# 01_giris.net
KiCad netlist of a schematic drawn in Altium Designer
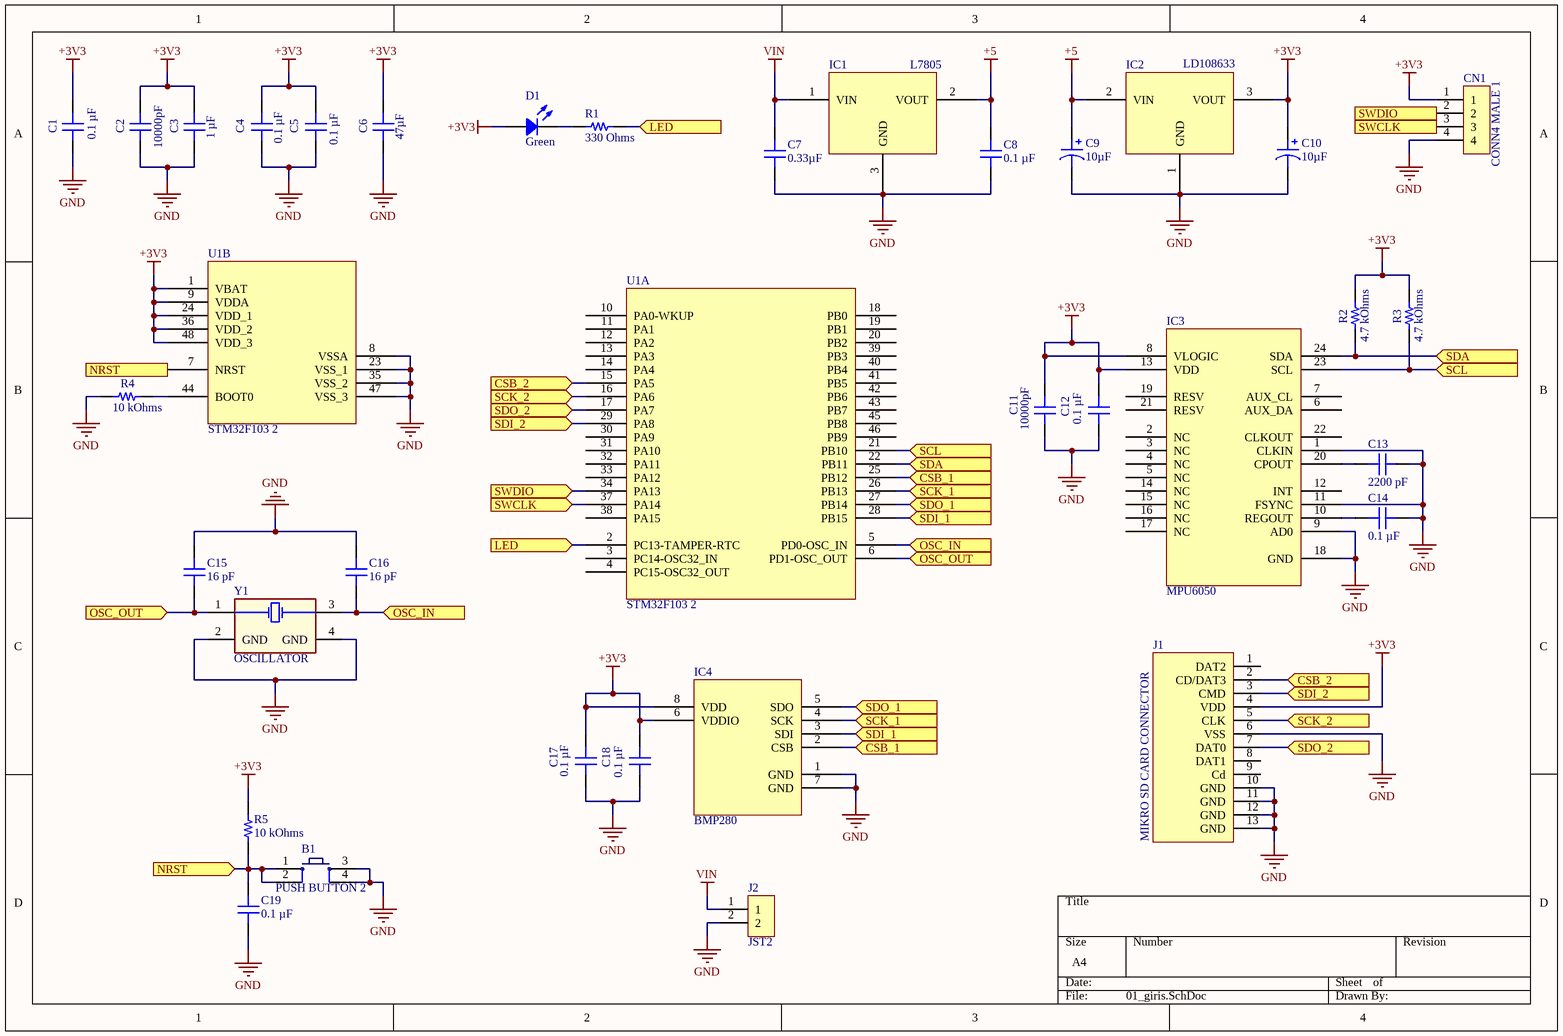
[diagram p0: 01_giris.SchDoc]

(export (version "E")
  (design (tool "Eeschema 10.0.6"))
  (components
    (comp (ref "B1")
      (value "PUSH BUTTON 2")
      (footprint "PUSH BUTTON 2")
      (libsource (lib "AltiumilePcbCizimi_Library") (part "PUSH BUTTON 2"))
    )
    (comp (ref "C1")
      (value "0.1 µF")
      (footprint "CAP 1206_3216 - 0.8MM")
      (description "CAP CER 0.1UF 50V X7R 1206")
      (fields
        (field (name "PART NUMBER") "1206B104M500CT")
        (field (name "MANUFACTURER") "Walsin Technology Corporation")
      )
      (libsource (lib "Celestial Altium Library - altium_library") (part "Capacitor"))
    )
    (comp (ref "C2")
      (value "10000pF")
      (footprint "CAP 1206_3216 - 1.0MM")
      (description "CAP CER 10000PF 50V X7R 1206")
      (fields (field (name "PART NUMBER") "12065C103K4T2A") (field (name "MANUFACTURER") "AVX Corporation"))
      (libsource (lib "Celestial Altium Library - altium_library") (part "Capacitor"))
    )
    (comp (ref "C3")
      (value "1 µF")
      (footprint "CAP 1206_3216 - 0.8MM")
      (description "CAP CER 1206 1UF 25V X7R")
      (fields (field (name "PART NUMBER") "C1206X105K3RAC3316") (field (name "MANUFACTURER") "KEMET"))
      (libsource (lib "Celestial Altium Library - altium_library") (part "Capacitor"))
    )
    (comp (ref "C4")
      (value "0.1 µF")
      (footprint "CAP 1206_3216 - 0.8MM")
      (description "CAP CER 0.1UF 50V X7R 1206")
      (fields
        (field (name "PART NUMBER") "1206B104M500CT")
        (field (name "MANUFACTURER") "Walsin Technology Corporation")
      )
      (libsource (lib "Celestial Altium Library - altium_library") (part "Capacitor"))
    )
    (comp (ref "C5")
      (value "0.1 µF")
      (footprint "CAP 1206_3216 - 0.8MM")
      (description "CAP CER 0.1UF 50V X7R 1206")
      (fields
        (field (name "PART NUMBER") "1206B104M500CT")
        (field (name "MANUFACTURER") "Walsin Technology Corporation")
      )
      (libsource (lib "Celestial Altium Library - altium_library") (part "Capacitor"))
    )
    (comp (ref "C6")
      (value "47µF")
      (footprint "CAP 1206_3216 - 1.8MM")
      (description "CAP CER 47UF 6.3V X5R 1206")
      (fields (field (name "PART NUMBER") "12066D476MAT2A") (field (name "MANUFACTURER") "AVX Corporation"))
      (libsource (lib "Celestial Altium Library - altium_library") (part "Capacitor"))
    )
    (comp (ref "C7")
      (value "0.33µF")
      (footprint "CAP 1206_3216 - 1.0MM")
      (description "CAP CER 0.33UF 50V Z5U 1206")
      (fields (field (name "PART NUMBER") "12065E334MAT2A") (field (name "MANUFACTURER") "AVX Corporation"))
      (libsource (lib "Celestial Altium Library - altium_library") (part "Capacitor"))
    )
    (comp (ref "C8")
      (value "0.1 µF")
      (footprint "CAP 1206_3216 - 0.8MM")
      (description "CAP CER 0.1UF 50V X7R 1206")
      (fields
        (field (name "PART NUMBER") "1206B104M500CT")
        (field (name "MANUFACTURER") "Walsin Technology Corporation")
      )
      (libsource (lib "Celestial Altium Library - altium_library") (part "Capacitor"))
    )
    (comp (ref "C9")
      (value "10µF")
      (footprint "CAP POL 1206_3216")
      (description "CAP TANT 10UF 20% 25V 1206")
      (fields (field (name "PART NUMBER") "F951E106MAAAQ2") (field (name "MANUFACTURER") "AVX Corporation"))
      (libsource (lib "Celestial Altium Library - altium_library") (part "Polarised Capacitor"))
    )
    (comp (ref "C10")
      (value "10µF")
      (footprint "CAP POL 1206_3216")
      (description "CAP TANT 10UF 20% 25V 1206")
      (fields (field (name "PART NUMBER") "F951E106MAAAQ2") (field (name "MANUFACTURER") "AVX Corporation"))
      (libsource (lib "Celestial Altium Library - altium_library") (part "Polarised Capacitor"))
    )
    (comp (ref "C11")
      (value "10000pF")
      (footprint "CAP 1206_3216 - 1.0MM")
      (description "CAP CER 10000PF 50V X7R 1206")
      (fields (field (name "PART NUMBER") "12065C103K4T2A") (field (name "MANUFACTURER") "AVX Corporation"))
      (libsource (lib "Celestial Altium Library - altium_library") (part "Capacitor"))
    )
    (comp (ref "C12")
      (value "0.1 µF")
      (footprint "CAP 1206_3216 - 0.8MM")
      (description "CAP CER 0.1UF 50V X7R 1206")
      (fields
        (field (name "PART NUMBER") "1206B104M500CT")
        (field (name "MANUFACTURER") "Walsin Technology Corporation")
      )
      (libsource (lib "Celestial Altium Library - altium_library") (part "Capacitor"))
    )
    (comp (ref "C13")
      (value "2200 pF")
      (footprint "CAP 1206_3216 - 0.8MM")
      (description "CAP CER 2200PF 50V C0G/NP0 1206")
      (fields
        (field (name "PART NUMBER") "CL31C222JBCNNNC")
        (field (name "MANUFACTURER") "Samsung Electro-Mechanics")
      )
      (libsource (lib "Celestial Altium Library - altium_library") (part "Capacitor"))
    )
    (comp (ref "C14")
      (value "0.1 µF")
      (footprint "CAP 1206_3216 - 0.8MM")
      (description "CAP CER 0.1UF 50V X7R 1206")
      (fields
        (field (name "PART NUMBER") "1206B104M500CT")
        (field (name "MANUFACTURER") "Walsin Technology Corporation")
      )
      (libsource (lib "Celestial Altium Library - altium_library") (part "Capacitor"))
    )
    (comp (ref "C15")
      (value "16 pF")
      (footprint "CAP 1206_3216 - 0.8MM")
      (description "CAP CER 16PF 50V NP0 1206")
      (fields (field (name "PART NUMBER") "C1206C160J5GAC7800") (field (name "MANUFACTURER") "KEMET"))
      (libsource (lib "Celestial Altium Library - altium_library") (part "Capacitor"))
    )
    (comp (ref "C16")
      (value "16 pF")
      (footprint "CAP 1206_3216 - 0.8MM")
      (description "CAP CER 16PF 50V NP0 1206")
      (fields (field (name "PART NUMBER") "C1206C160J5GAC7800") (field (name "MANUFACTURER") "KEMET"))
      (libsource (lib "Celestial Altium Library - altium_library") (part "Capacitor"))
    )
    (comp (ref "C17")
      (value "0.1 µF")
      (footprint "CAP 1206_3216 - 0.8MM")
      (description "CAP CER 0.1UF 50V X7R 1206")
      (fields
        (field (name "PART NUMBER") "1206B104M500CT")
        (field (name "MANUFACTURER") "Walsin Technology Corporation")
      )
      (libsource (lib "Celestial Altium Library - altium_library") (part "Capacitor"))
    )
    (comp (ref "C18")
      (value "0.1 µF")
      (footprint "CAP 1206_3216 - 0.8MM")
      (description "CAP CER 0.1UF 50V X7R 1206")
      (fields
        (field (name "PART NUMBER") "1206B104M500CT")
        (field (name "MANUFACTURER") "Walsin Technology Corporation")
      )
      (libsource (lib "Celestial Altium Library - altium_library") (part "Capacitor"))
    )
    (comp (ref "C19")
      (value "0.1 µF")
      (footprint "CAP 1206_3216 - 0.8MM")
      (description "CAP CER 0.1UF 50V X7R 1206")
      (fields
        (field (name "PART NUMBER") "1206B104M500CT")
        (field (name "MANUFACTURER") "Walsin Technology Corporation")
      )
      (libsource (lib "Celestial Altium Library - altium_library") (part "Capacitor"))
    )
    (comp (ref "CN1")
      (value "CONN4 MALE 1")
      (footprint "CONN4 MALE 1")
      (description "4 PIN 2.54MM")
      (libsource (lib "AltiumilePcbCizimi_Library") (part "CONN4 MALE 1"))
    )
    (comp (ref "D1")
      (value "Green")
      (footprint "LED 0805_2012 GREEN")
      (description "LED GREEN 0805 SMD")
      (fields (field (name "PART NUMBER") "5975316507F") (field (name "MANUFACTURER") "Dialight"))
      (libsource (lib "Celestial Altium Library - altium_library") (part "LED"))
    )
    (comp (ref "IC1")
      (value "L7805")
      (footprint "DPAK")
      (description "IC-7805 V.REG.+5V 1.5A DPAK TO252")
      (libsource (lib "AltiumilePcbCizimi_Library") (part "L7805"))
    )
    (comp (ref "IC2")
      (value "LD108633")
      (footprint "DPAK")
      (description "IC-1086 V.REG LDO 3.3V 1.5A TO-252 (DPAK)")
      (libsource (lib "AltiumilePcbCizimi_Library") (part "LD108633"))
    )
    (comp (ref "IC3")
      (value "MPU6050")
      (footprint "QFN")
      (description "IC-6050 SENSOR MOTION QFN24")
      (libsource (lib "AltiumilePcbCizimi_Library") (part "MPU6050"))
    )
    (comp (ref "IC4")
      (value "BMP280")
      (footprint "BMP280")
      (libsource (lib "AltiumilePcbCizimi_Library") (part "BMP280"))
    )
    (comp (ref "J1")
      (value "MIKRO SD CARD CONNECTOR")
      (footprint "MICRO SD CARD CONNECTOR")
      (libsource (lib "AltiumilePcbCizimi_Library") (part "MIKRO SD CARD CONNECTOR"))
    )
    (comp (ref "J2")
      (value "JST2")
      (footprint "JST2")
      (description "2 PIN 2.54MM")
      (libsource (lib "AltiumilePcbCizimi_Library") (part "JST2"))
    )
    (comp (ref "R1")
      (value "330 Ohms")
      (footprint "RES 0805_2012")
      (description "RES SMD 330 OHM 1% 1/8W 0805")
      (fields (field (name "PART NUMBER") "AC0805FR-07330RL") (field (name "MANUFACTURER") "Yageo"))
      (libsource (lib "Celestial Altium Library - altium_library") (part "Resistor"))
    )
    (comp (ref "R2")
      (value "4.7 kOhms")
      (footprint "RES 1206_3216")
      (description "RES 4.7K OHM 0.1% 2/5W 1206")
      (fields (field (name "PART NUMBER") "TNPW12064K70BEEA") (field (name "MANUFACTURER") "Vishay Dale"))
      (libsource (lib "Celestial Altium Library - altium_library") (part "Resistor"))
    )
    (comp (ref "R3")
      (value "4.7 kOhms")
      (footprint "RES 1206_3216")
      (description "RES 4.7K OHM 0.1% 2/5W 1206")
      (fields (field (name "PART NUMBER") "TNPW12064K70BEEA") (field (name "MANUFACTURER") "Vishay Dale"))
      (libsource (lib "Celestial Altium Library - altium_library") (part "Resistor"))
    )
    (comp (ref "R4")
      (value "10 kOhms")
      (footprint "RES 1206_3216")
      (description "RES SMD 10K OHM 1% 1/4W 1206")
      (fields (field (name "PART NUMBER") "CRCW120610K0FKTA") (field (name "MANUFACTURER") "Vishay Dale"))
      (libsource (lib "Celestial Altium Library - altium_library") (part "Resistor"))
    )
    (comp (ref "R5")
      (value "10 kOhms")
      (footprint "RES 1206_3216")
      (description "RES SMD 10K OHM 1% 1/4W 1206")
      (fields (field (name "PART NUMBER") "CRCW120610K0FKTA") (field (name "MANUFACTURER") "Vishay Dale"))
      (libsource (lib "Celestial Altium Library - altium_library") (part "Resistor"))
    )
    (comp (ref "U1")
      (value "STM32F103 2")
      (footprint "LQFP48")
      (libsource (lib "AltiumilePcbCizimi_Library") (part "STM32F103 2"))
    )
    (comp (ref "Y1")
      (value "OSCILLATOR")
      (footprint "OSCILLATOR")
      (description "8MHZ 12.5pF")
      (libsource (lib "AltiumilePcbCizimi_Library") (part "OSCILLATOR"))
    )
  )
  (nets
    (net (code "1") (name "+3V3") (class "Default")
      (node (ref "C1") (pin "2") (pinfunction "2_2") (pintype "passive"))
      (node (ref "C10") (pin "1") (pinfunction "1_1") (pintype "passive"))
      (node (ref "C11") (pin "2") (pinfunction "2_2") (pintype "passive"))
      (node (ref "C12") (pin "1") (pinfunction "1_1") (pintype "passive"))
      (node (ref "C17") (pin "2") (pinfunction "2_2") (pintype "passive"))
      (node (ref "C18") (pin "2") (pinfunction "2_2") (pintype "passive"))
      (node (ref "C2") (pin "2") (pinfunction "2_2") (pintype "passive"))
      (node (ref "C3") (pin "2") (pinfunction "2_2") (pintype "passive"))
      (node (ref "C4") (pin "2") (pinfunction "2_2") (pintype "passive"))
      (node (ref "C5") (pin "2") (pinfunction "2_2") (pintype "passive"))
      (node (ref "C6") (pin "2") (pinfunction "2_2") (pintype "passive"))
      (node (ref "CN1") (pin "1") (pinfunction "1_1") (pintype "passive"))
      (node (ref "D1") (pin "1") (pinfunction "1_1") (pintype "passive"))
      (node (ref "IC2") (pin "3") (pinfunction "VOUT_3") (pintype "passive"))
      (node (ref "IC3") (pin "13") (pinfunction "VDD_13") (pintype "passive"))
      (node (ref "IC3") (pin "8") (pinfunction "VLOGIC_8") (pintype "passive"))
      (node (ref "IC4") (pin "6") (pinfunction "VDDIO_6") (pintype "passive"))
      (node (ref "IC4") (pin "8") (pinfunction "VDD_8") (pintype "passive"))
      (node (ref "J1") (pin "4") (pinfunction "VDD_4") (pintype "passive"))
      (node (ref "R2") (pin "2") (pinfunction "2_2") (pintype "passive"))
      (node (ref "R3") (pin "2") (pinfunction "2_2") (pintype "passive"))
      (node (ref "R5") (pin "2") (pinfunction "2_2") (pintype "passive"))
      (node (ref "U1") (pin "1") (pinfunction "VBAT_1") (pintype "passive"))
      (node (ref "U1") (pin "24") (pinfunction "VDD_1_24") (pintype "passive"))
      (node (ref "U1") (pin "36") (pinfunction "VDD_2_36") (pintype "passive"))
      (node (ref "U1") (pin "48") (pinfunction "VDD_3_48") (pintype "passive"))
      (node (ref "U1") (pin "9") (pinfunction "VDDA_9") (pintype "passive"))
    )
    (net (code "2") (name "+5") (class "Default")
      (node (ref "C8") (pin "2") (pinfunction "2_2") (pintype "passive"))
      (node (ref "C9") (pin "1") (pinfunction "1_1") (pintype "passive"))
      (node (ref "IC1") (pin "2") (pinfunction "VOUT_2") (pintype "passive"))
      (node (ref "IC2") (pin "2") (pinfunction "VIN_2") (pintype "passive"))
    )
    (net (code "3") (name "/CSB_1") (class "Default")
      (node (ref "IC4") (pin "2") (pinfunction "CSB_2") (pintype "passive"))
      (node (ref "U1") (pin "25") (pinfunction "PB12_25") (pintype "passive"))
    )
    (net (code "4") (name "/CSB_2") (class "Default")
      (node (ref "J1") (pin "2") (pinfunction "CD/DAT3_2") (pintype "passive"))
      (node (ref "U1") (pin "15") (pinfunction "PA5_15") (pintype "passive"))
    )
    (net (code "5") (name "/LED") (class "Default")
      (node (ref "R1") (pin "2") (pinfunction "2_2") (pintype "passive"))
      (node (ref "U1") (pin "2") (pinfunction "PC13-TAMPER-RTC_2") (pintype "passive"))
    )
    (net (code "6") (name "/NRST") (class "Default")
      (node (ref "B1") (pin "1") (pinfunction "1_1") (pintype "passive"))
      (node (ref "B1") (pin "2") (pinfunction "2_2") (pintype "passive"))
      (node (ref "C19") (pin "2") (pinfunction "2_2") (pintype "passive"))
      (node (ref "R5") (pin "1") (pinfunction "1_1") (pintype "passive"))
      (node (ref "U1") (pin "7") (pinfunction "NRST_7") (pintype "passive"))
    )
    (net (code "7") (name "/OSC_IN") (class "Default")
      (node (ref "C16") (pin "1") (pinfunction "1_1") (pintype "passive"))
      (node (ref "U1") (pin "5") (pinfunction "PD0-OSC_IN_5") (pintype "passive"))
      (node (ref "Y1") (pin "3") (pintype "passive"))
    )
    (net (code "8") (name "/OSC_OUT") (class "Default")
      (node (ref "C15") (pin "1") (pinfunction "1_1") (pintype "passive"))
      (node (ref "U1") (pin "6") (pinfunction "PD1-OSC_OUT_6") (pintype "passive"))
      (node (ref "Y1") (pin "1") (pintype "power_in"))
    )
    (net (code "9") (name "/SCK_1") (class "Default")
      (node (ref "IC4") (pin "4") (pinfunction "SCK_4") (pintype "passive"))
      (node (ref "U1") (pin "26") (pinfunction "PB13_26") (pintype "passive"))
    )
    (net (code "10") (name "/SCK_2") (class "Default")
      (node (ref "J1") (pin "5") (pinfunction "CLK_5") (pintype "passive"))
      (node (ref "U1") (pin "16") (pinfunction "PA6_16") (pintype "passive"))
    )
    (net (code "11") (name "/SCL") (class "Default")
      (node (ref "IC3") (pin "23") (pinfunction "SCL_23") (pintype "passive"))
      (node (ref "R3") (pin "1") (pinfunction "1_1") (pintype "passive"))
      (node (ref "U1") (pin "21") (pinfunction "PB10_21") (pintype "passive"))
    )
    (net (code "12") (name "/SDA") (class "Default")
      (node (ref "IC3") (pin "24") (pinfunction "SDA_24") (pintype "passive"))
      (node (ref "R2") (pin "1") (pinfunction "1_1") (pintype "passive"))
      (node (ref "U1") (pin "22") (pinfunction "PB11_22") (pintype "passive"))
    )
    (net (code "13") (name "/SDI_1") (class "Default")
      (node (ref "IC4") (pin "3") (pinfunction "SDI_3") (pintype "passive"))
      (node (ref "U1") (pin "28") (pinfunction "PB15_28") (pintype "passive"))
    )
    (net (code "14") (name "/SDI_2") (class "Default")
      (node (ref "J1") (pin "3") (pinfunction "CMD_3") (pintype "passive"))
      (node (ref "U1") (pin "29") (pinfunction "PA8_29") (pintype "passive"))
    )
    (net (code "15") (name "/SDO_1") (class "Default")
      (node (ref "IC4") (pin "5") (pinfunction "SDO_5") (pintype "passive"))
      (node (ref "U1") (pin "27") (pinfunction "PB14_27") (pintype "passive"))
    )
    (net (code "16") (name "/SDO_2") (class "Default")
      (node (ref "J1") (pin "7") (pinfunction "DAT0_7") (pintype "passive"))
      (node (ref "U1") (pin "17") (pinfunction "PA7_17") (pintype "passive"))
    )
    (net (code "17") (name "/SWCLK") (class "Default")
      (node (ref "CN1") (pin "3") (pinfunction "3_3") (pintype "passive"))
      (node (ref "U1") (pin "37") (pinfunction "PA14_37") (pintype "passive"))
    )
    (net (code "18") (name "/SWDIO") (class "Default")
      (node (ref "CN1") (pin "2") (pinfunction "2_2") (pintype "passive"))
      (node (ref "U1") (pin "34") (pinfunction "PA13_34") (pintype "passive"))
    )
    (net (code "19") (name "GND") (class "Default")
      (node (ref "B1") (pin "3") (pinfunction "3_3") (pintype "passive"))
      (node (ref "B1") (pin "4") (pinfunction "4_4") (pintype "passive"))
      (node (ref "C1") (pin "1") (pinfunction "1_1") (pintype "passive"))
      (node (ref "C10") (pin "2") (pinfunction "2_2") (pintype "passive"))
      (node (ref "C11") (pin "1") (pinfunction "1_1") (pintype "passive"))
      (node (ref "C12") (pin "2") (pinfunction "2_2") (pintype "passive"))
      (node (ref "C13") (pin "2") (pinfunction "2_2") (pintype "passive"))
      (node (ref "C14") (pin "2") (pinfunction "2_2") (pintype "passive"))
      (node (ref "C15") (pin "2") (pinfunction "2_2") (pintype "passive"))
      (node (ref "C16") (pin "2") (pinfunction "2_2") (pintype "passive"))
      (node (ref "C17") (pin "1") (pinfunction "1_1") (pintype "passive"))
      (node (ref "C18") (pin "1") (pinfunction "1_1") (pintype "passive"))
      (node (ref "C19") (pin "1") (pinfunction "1_1") (pintype "passive"))
      (node (ref "C2") (pin "1") (pinfunction "1_1") (pintype "passive"))
      (node (ref "C3") (pin "1") (pinfunction "1_1") (pintype "passive"))
      (node (ref "C4") (pin "1") (pinfunction "1_1") (pintype "passive"))
      (node (ref "C5") (pin "1") (pinfunction "1_1") (pintype "passive"))
      (node (ref "C6") (pin "1") (pinfunction "1_1") (pintype "passive"))
      (node (ref "C7") (pin "1") (pinfunction "1_1") (pintype "passive"))
      (node (ref "C8") (pin "1") (pinfunction "1_1") (pintype "passive"))
      (node (ref "C9") (pin "2") (pinfunction "2_2") (pintype "passive"))
      (node (ref "CN1") (pin "4") (pinfunction "4_4") (pintype "passive"))
      (node (ref "IC1") (pin "3") (pinfunction "GND_3") (pintype "passive"))
      (node (ref "IC2") (pin "1") (pinfunction "GND_1") (pintype "passive"))
      (node (ref "IC3") (pin "1") (pinfunction "CLKIN_1") (pintype "passive"))
      (node (ref "IC3") (pin "11") (pinfunction "FSYNC_11") (pintype "passive"))
      (node (ref "IC3") (pin "18") (pinfunction "GND_18") (pintype "passive"))
      (node (ref "IC3") (pin "9") (pinfunction "AD0_9") (pintype "passive"))
      (node (ref "IC4") (pin "1") (pinfunction "GND_1") (pintype "passive"))
      (node (ref "IC4") (pin "7") (pinfunction "GND_7") (pintype "passive"))
      (node (ref "J1") (pin "10") (pinfunction "GND_10") (pintype "passive"))
      (node (ref "J1") (pin "11") (pinfunction "GND_11") (pintype "passive"))
      (node (ref "J1") (pin "12") (pinfunction "GND_12") (pintype "passive"))
      (node (ref "J1") (pin "13") (pinfunction "GND_13") (pintype "passive"))
      (node (ref "J1") (pin "6") (pinfunction "VSS_6") (pintype "passive"))
      (node (ref "J2") (pin "2") (pinfunction "2_2") (pintype "passive"))
      (node (ref "R4") (pin "1") (pinfunction "1_1") (pintype "passive"))
      (node (ref "U1") (pin "23") (pinfunction "VSS_1_23") (pintype "passive"))
      (node (ref "U1") (pin "35") (pinfunction "VSS_2_35") (pintype "passive"))
      (node (ref "U1") (pin "47") (pinfunction "VSS_3_47") (pintype "passive"))
      (node (ref "U1") (pin "8") (pinfunction "VSSA_8") (pintype "passive"))
      (node (ref "Y1") (pin "2") (pinfunction "GND_2") (pintype "power_in"))
      (node (ref "Y1") (pin "4") (pinfunction "GND_4") (pintype "passive"))
    )
    (net (code "20") (name "Net-(D1-Pad2)") (class "Default")
      (node (ref "D1") (pin "2") (pinfunction "2_2") (pintype "passive"))
      (node (ref "R1") (pin "1") (pinfunction "1_1") (pintype "passive"))
    )
    (net (code "21") (name "Net-(IC3-CPOUT)") (class "Default")
      (node (ref "C13") (pin "1") (pinfunction "1_1") (pintype "passive"))
      (node (ref "IC3") (pin "20") (pinfunction "CPOUT_20") (pintype "passive"))
    )
    (net (code "22") (name "Net-(IC3-REGOUT)") (class "Default")
      (node (ref "C14") (pin "1") (pinfunction "1_1") (pintype "passive"))
      (node (ref "IC3") (pin "10") (pinfunction "REGOUT_10") (pintype "passive"))
    )
    (net (code "23") (name "Net-(U1B-BOOT0)") (class "Default")
      (node (ref "R4") (pin "2") (pinfunction "2_2") (pintype "passive"))
      (node (ref "U1") (pin "44") (pinfunction "BOOT0_44") (pintype "passive"))
    )
    (net (code "24") (name "VIN") (class "Default")
      (node (ref "C7") (pin "2") (pinfunction "2_2") (pintype "passive"))
      (node (ref "IC1") (pin "1") (pinfunction "VIN_1") (pintype "passive"))
      (node (ref "J2") (pin "1") (pinfunction "1_1") (pintype "passive"))
    )
    (net (code "25") (name "unconnected-(IC3-AUX_CL-Pad7)") (class "Default")
      (node (ref "IC3") (pin "7") (pinfunction "AUX_CL_7") (pintype "passive"))
    )
    (net (code "26") (name "unconnected-(IC3-AUX_DA-Pad6)") (class "Default")
      (node (ref "IC3") (pin "6") (pinfunction "AUX_DA_6") (pintype "passive"))
    )
    (net (code "27") (name "unconnected-(IC3-CLKOUT-Pad22)") (class "Default")
      (node (ref "IC3") (pin "22") (pinfunction "CLKOUT_22") (pintype "passive"))
    )
    (net (code "28") (name "unconnected-(IC3-INT-Pad12)") (class "Default")
      (node (ref "IC3") (pin "12") (pinfunction "INT_12") (pintype "passive"))
    )
    (net (code "29") (name "unconnected-(IC3-NC-Pad2)") (class "Default")
      (node (ref "IC3") (pin "2") (pinfunction "NC_2") (pintype "passive"))
    )
    (net (code "30") (name "unconnected-(IC3-NC-Pad3)") (class "Default")
      (node (ref "IC3") (pin "3") (pinfunction "NC_3") (pintype "passive"))
    )
    (net (code "31") (name "unconnected-(IC3-NC-Pad4)") (class "Default")
      (node (ref "IC3") (pin "4") (pinfunction "NC_4") (pintype "passive"))
    )
    (net (code "32") (name "unconnected-(IC3-NC-Pad5)") (class "Default")
      (node (ref "IC3") (pin "5") (pinfunction "NC_5") (pintype "passive"))
    )
    (net (code "33") (name "unconnected-(IC3-NC-Pad14)") (class "Default")
      (node (ref "IC3") (pin "14") (pinfunction "NC_14") (pintype "passive"))
    )
    (net (code "34") (name "unconnected-(IC3-NC-Pad15)") (class "Default")
      (node (ref "IC3") (pin "15") (pinfunction "NC_15") (pintype "passive"))
    )
    (net (code "35") (name "unconnected-(IC3-NC-Pad16)") (class "Default")
      (node (ref "IC3") (pin "16") (pinfunction "NC_16") (pintype "passive"))
    )
    (net (code "36") (name "unconnected-(IC3-NC-Pad17)") (class "Default")
      (node (ref "IC3") (pin "17") (pinfunction "NC_17") (pintype "passive"))
    )
    (net (code "37") (name "unconnected-(IC3-RESV-Pad19)") (class "Default")
      (node (ref "IC3") (pin "19") (pinfunction "RESV_19") (pintype "passive"))
    )
    (net (code "38") (name "unconnected-(IC3-RESV-Pad21)") (class "Default")
      (node (ref "IC3") (pin "21") (pinfunction "RESV_21") (pintype "passive"))
    )
    (net (code "39") (name "unconnected-(J1-Cd-Pad9)") (class "Default")
      (node (ref "J1") (pin "9") (pinfunction "Cd_9") (pintype "passive"))
    )
    (net (code "40") (name "unconnected-(J1-DAT1-Pad8)") (class "Default")
      (node (ref "J1") (pin "8") (pinfunction "DAT1_8") (pintype "passive"))
    )
    (net (code "41") (name "unconnected-(J1-DAT2-Pad1)") (class "Default")
      (node (ref "J1") (pin "1") (pinfunction "DAT2_1") (pintype "passive"))
    )
    (net (code "42") (name "unconnected-(U1A-PA0-WKUP-Pad10)") (class "Default")
      (node (ref "U1") (pin "10") (pinfunction "PA0-WKUP_10") (pintype "passive"))
    )
    (net (code "43") (name "unconnected-(U1A-PA1-Pad11)") (class "Default")
      (node (ref "U1") (pin "11") (pinfunction "PA1_11") (pintype "passive"))
    )
    (net (code "44") (name "unconnected-(U1A-PA2-Pad12)") (class "Default")
      (node (ref "U1") (pin "12") (pinfunction "PA2_12") (pintype "passive"))
    )
    (net (code "45") (name "unconnected-(U1A-PA3-Pad13)") (class "Default")
      (node (ref "U1") (pin "13") (pinfunction "PA3_13") (pintype "passive"))
    )
    (net (code "46") (name "unconnected-(U1A-PA4-Pad14)") (class "Default")
      (node (ref "U1") (pin "14") (pinfunction "PA4_14") (pintype "passive"))
    )
    (net (code "47") (name "unconnected-(U1A-PA9-Pad30)") (class "Default")
      (node (ref "U1") (pin "30") (pinfunction "PA9_30") (pintype "passive"))
    )
    (net (code "48") (name "unconnected-(U1A-PA10-Pad31)") (class "Default")
      (node (ref "U1") (pin "31") (pinfunction "PA10_31") (pintype "passive"))
    )
    (net (code "49") (name "unconnected-(U1A-PA11-Pad32)") (class "Default")
      (node (ref "U1") (pin "32") (pinfunction "PA11_32") (pintype "passive"))
    )
    (net (code "50") (name "unconnected-(U1A-PA12-Pad33)") (class "Default")
      (node (ref "U1") (pin "33") (pinfunction "PA12_33") (pintype "passive"))
    )
    (net (code "51") (name "unconnected-(U1A-PA15-Pad38)") (class "Default")
      (node (ref "U1") (pin "38") (pinfunction "PA15_38") (pintype "passive"))
    )
    (net (code "52") (name "unconnected-(U1A-PB0-Pad18)") (class "Default")
      (node (ref "U1") (pin "18") (pinfunction "PB0_18") (pintype "passive"))
    )
    (net (code "53") (name "unconnected-(U1A-PB1-Pad19)") (class "Default")
      (node (ref "U1") (pin "19") (pinfunction "PB1_19") (pintype "passive"))
    )
    (net (code "54") (name "unconnected-(U1A-PB2-Pad20)") (class "Default")
      (node (ref "U1") (pin "20") (pinfunction "PB2_20") (pintype "passive"))
    )
    (net (code "55") (name "unconnected-(U1A-PB3-Pad39)") (class "Default")
      (node (ref "U1") (pin "39") (pinfunction "PB3_39") (pintype "passive"))
    )
    (net (code "56") (name "unconnected-(U1A-PB4-Pad40)") (class "Default")
      (node (ref "U1") (pin "40") (pinfunction "PB4_40") (pintype "passive"))
    )
    (net (code "57") (name "unconnected-(U1A-PB5-Pad41)") (class "Default")
      (node (ref "U1") (pin "41") (pinfunction "PB5_41") (pintype "passive"))
    )
    (net (code "58") (name "unconnected-(U1A-PB6-Pad42)") (class "Default")
      (node (ref "U1") (pin "42") (pinfunction "PB6_42") (pintype "passive"))
    )
    (net (code "59") (name "unconnected-(U1A-PB7-Pad43)") (class "Default")
      (node (ref "U1") (pin "43") (pinfunction "PB7_43") (pintype "passive"))
    )
    (net (code "60") (name "unconnected-(U1A-PB8-Pad45)") (class "Default")
      (node (ref "U1") (pin "45") (pinfunction "PB8_45") (pintype "passive"))
    )
    (net (code "61") (name "unconnected-(U1A-PB9-Pad46)") (class "Default")
      (node (ref "U1") (pin "46") (pinfunction "PB9_46") (pintype "passive"))
    )
    (net (code "62") (name "unconnected-(U1A-PC14-OSC32_IN-Pad3)") (class "Default")
      (node (ref "U1") (pin "3") (pinfunction "PC14-OSC32_IN_3") (pintype "passive"))
    )
    (net (code "63") (name "unconnected-(U1A-PC15-OSC32_OUT-Pad4)") (class "Default")
      (node (ref "U1") (pin "4") (pinfunction "PC15-OSC32_OUT_4") (pintype "passive"))
    )
  )
)
